# mosfet-drv.net
KiCad netlist of a schematic drawn in EAGLE
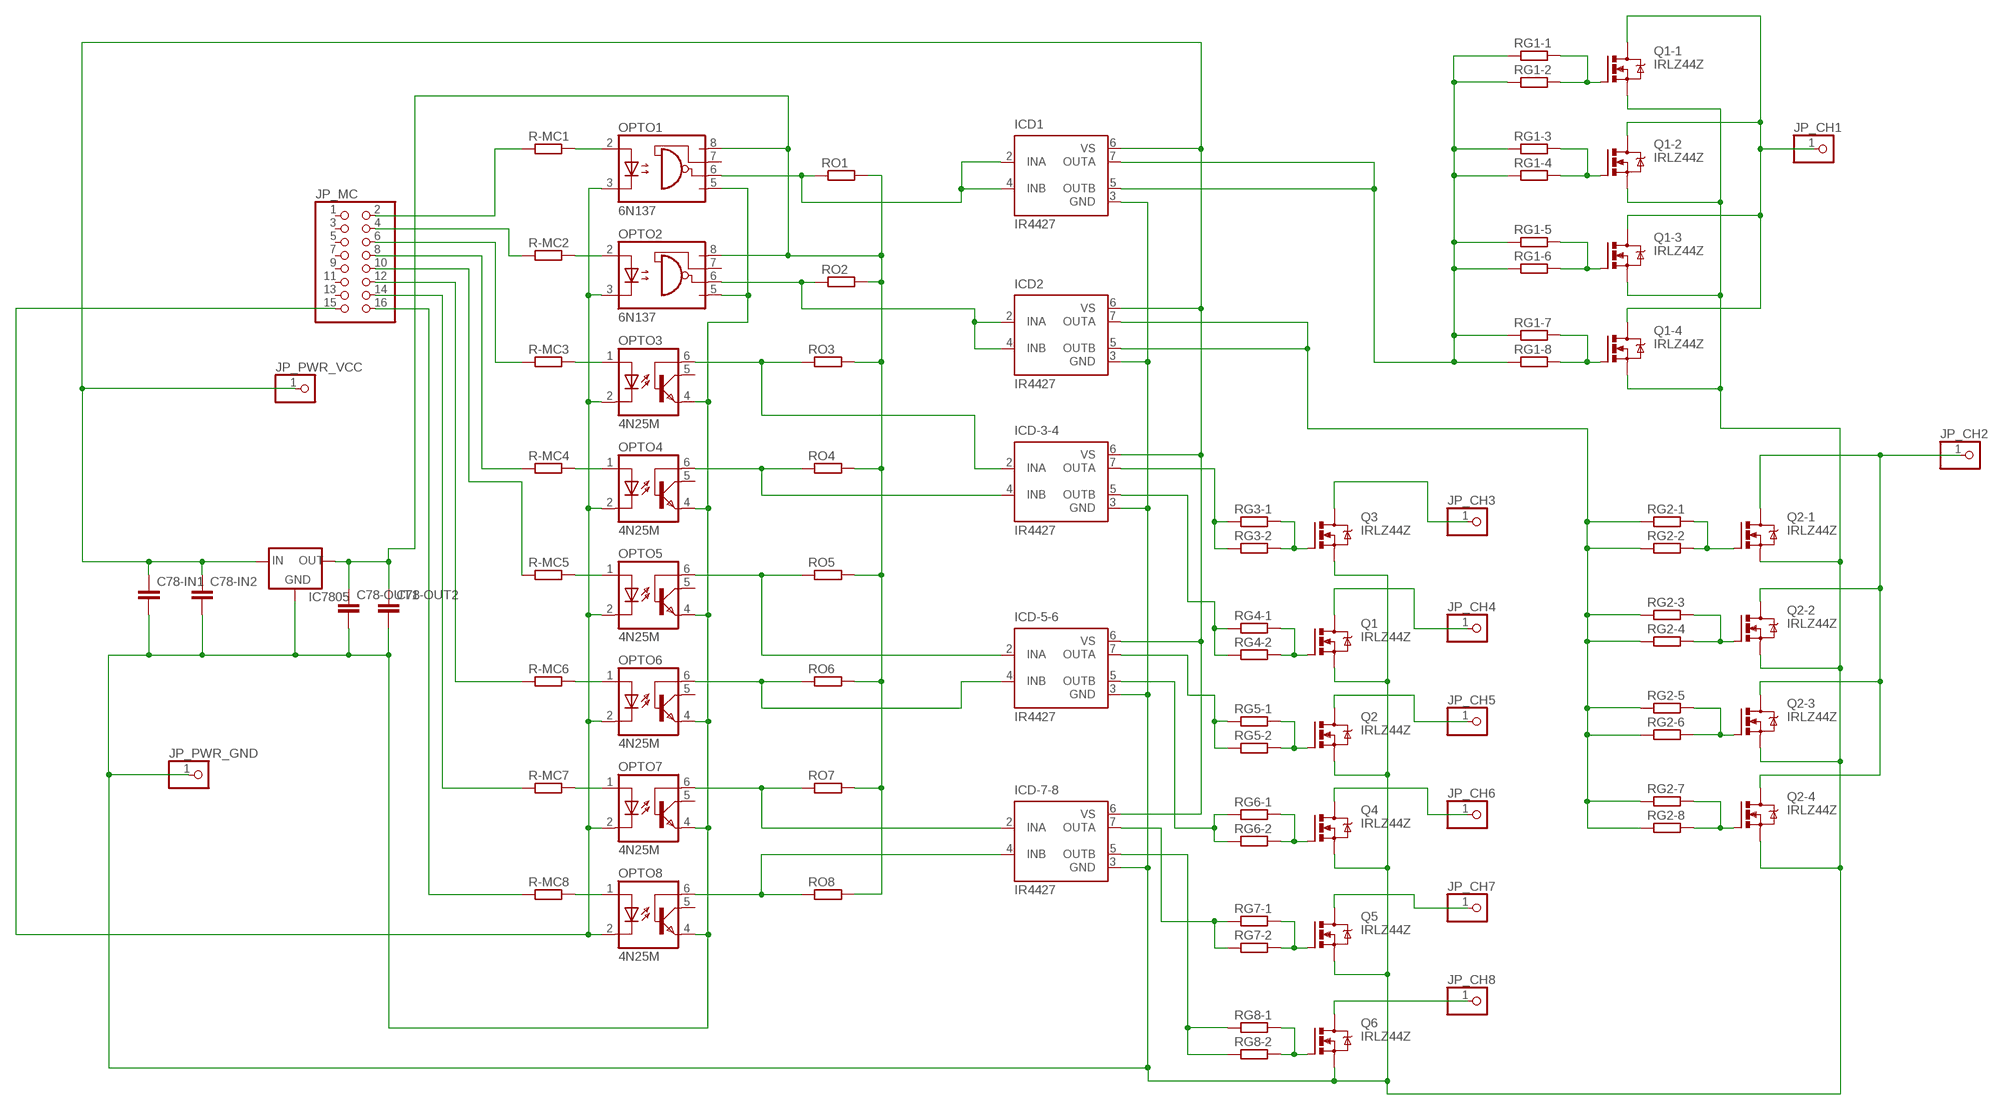
[diagram p0: schematic, sheet 1]

(export (version "E")
  (design (tool "Eeschema 10.0.6"))
  (components
    (comp (ref "C78-IN1")
      (value "C-EU025-060X050")
      (footprint "eagle-import:C025-060X050")
      (libsource (lib "eagle-import") (part "C-EU025-060X050"))
    )
    (comp (ref "C78-IN2")
      (value "C-EU025-060X050")
      (footprint "eagle-import:C025-060X050")
      (libsource (lib "eagle-import") (part "C-EU025-060X050"))
    )
    (comp (ref "C78-OUT1")
      (value "C-EU025-060X050")
      (footprint "eagle-import:C025-060X050")
      (libsource (lib "eagle-import") (part "C-EU025-060X050"))
    )
    (comp (ref "C78-OUT2")
      (value "C-EU025-060X050")
      (footprint "eagle-import:C025-060X050")
      (libsource (lib "eagle-import") (part "C-EU025-060X050"))
    )
    (comp (ref "IC7805")
      (value "78XXS")
      (footprint "eagle-import:78XXS")
      (libsource (lib "eagle-import") (part "78XXS"))
    )
    (comp (ref "ICD-3-4")
      (value "IR4427")
      (footprint "eagle-import:DIL08")
      (fields (field (name "MF") "INTERNATIONAL RECTIFIER(IR)"))
      (libsource (lib "eagle-import") (part "IR4427"))
    )
    (comp (ref "ICD-5-6")
      (value "IR4427")
      (footprint "eagle-import:DIL08")
      (fields (field (name "MF") "INTERNATIONAL RECTIFIER(IR)"))
      (libsource (lib "eagle-import") (part "IR4427"))
    )
    (comp (ref "ICD-7-8")
      (value "IR4427")
      (footprint "eagle-import:DIL08")
      (fields (field (name "MF") "INTERNATIONAL RECTIFIER(IR)"))
      (libsource (lib "eagle-import") (part "IR4427"))
    )
    (comp (ref "ICD1")
      (value "IR4427")
      (footprint "eagle-import:DIL08")
      (fields (field (name "MF") "INTERNATIONAL RECTIFIER(IR)"))
      (libsource (lib "eagle-import") (part "IR4427"))
    )
    (comp (ref "ICD2")
      (value "IR4427")
      (footprint "eagle-import:DIL08")
      (fields (field (name "MF") "INTERNATIONAL RECTIFIER(IR)"))
      (libsource (lib "eagle-import") (part "IR4427"))
    )
    (comp (ref "JP_CH1")
      (value "PINHD-1X1")
      (footprint "eagle-import:1X01")
      (libsource (lib "eagle-import") (part "PINHD-1X1"))
    )
    (comp (ref "JP_CH2")
      (value "PINHD-1X1")
      (footprint "eagle-import:1X01")
      (libsource (lib "eagle-import") (part "PINHD-1X1"))
    )
    (comp (ref "JP_CH3")
      (value "PINHD-1X1")
      (footprint "eagle-import:1X01")
      (libsource (lib "eagle-import") (part "PINHD-1X1"))
    )
    (comp (ref "JP_CH4")
      (value "PINHD-1X1")
      (footprint "eagle-import:1X01")
      (libsource (lib "eagle-import") (part "PINHD-1X1"))
    )
    (comp (ref "JP_CH5")
      (value "PINHD-1X1")
      (footprint "eagle-import:1X01")
      (libsource (lib "eagle-import") (part "PINHD-1X1"))
    )
    (comp (ref "JP_CH6")
      (value "PINHD-1X1")
      (footprint "eagle-import:1X01")
      (libsource (lib "eagle-import") (part "PINHD-1X1"))
    )
    (comp (ref "JP_CH7")
      (value "PINHD-1X1")
      (footprint "eagle-import:1X01")
      (libsource (lib "eagle-import") (part "PINHD-1X1"))
    )
    (comp (ref "JP_CH8")
      (value "PINHD-1X1")
      (footprint "eagle-import:1X01")
      (libsource (lib "eagle-import") (part "PINHD-1X1"))
    )
    (comp (ref "JP_MC")
      (value "PINHD-2X8")
      (footprint "eagle-import:2X08")
      (libsource (lib "eagle-import") (part "PINHD-2X8"))
    )
    (comp (ref "JP_PWR_GND")
      (value "PINHD-1X1")
      (footprint "eagle-import:1X01")
      (libsource (lib "eagle-import") (part "PINHD-1X1"))
    )
    (comp (ref "JP_PWR_VCC")
      (value "PINHD-1X1")
      (footprint "eagle-import:1X01")
      (libsource (lib "eagle-import") (part "PINHD-1X1"))
    )
    (comp (ref "OPTO1")
      (value "6N137")
      (footprint "eagle-import:DIL08")
      (libsource (lib "eagle-import") (part "6N137"))
    )
    (comp (ref "OPTO2")
      (value "6N137")
      (footprint "eagle-import:DIL08")
      (libsource (lib "eagle-import") (part "6N137"))
    )
    (comp (ref "OPTO3")
      (value "4N25M")
      (footprint "eagle-import:DIL06")
      (fields (field (name "MPN") "4N25-M"))
      (libsource (lib "eagle-import") (part "4N?M25"))
    )
    (comp (ref "OPTO4")
      (value "4N25M")
      (footprint "eagle-import:DIL06")
      (fields (field (name "MPN") "4N25-M"))
      (libsource (lib "eagle-import") (part "4N?M25"))
    )
    (comp (ref "OPTO5")
      (value "4N25M")
      (footprint "eagle-import:DIL06")
      (fields (field (name "MPN") "4N25-M"))
      (libsource (lib "eagle-import") (part "4N?M25"))
    )
    (comp (ref "OPTO6")
      (value "4N25M")
      (footprint "eagle-import:DIL06")
      (fields (field (name "MPN") "4N25-M"))
      (libsource (lib "eagle-import") (part "4N?M25"))
    )
    (comp (ref "OPTO7")
      (value "4N25M")
      (footprint "eagle-import:DIL06")
      (fields (field (name "MPN") "4N25-M"))
      (libsource (lib "eagle-import") (part "4N?M25"))
    )
    (comp (ref "OPTO8")
      (value "4N25M")
      (footprint "eagle-import:DIL06")
      (fields (field (name "MPN") "4N25-M"))
      (libsource (lib "eagle-import") (part "4N?M25"))
    )
    (comp (ref "Q1")
      (value "IRLZ44Z")
      (footprint "eagle-import:TO220BH")
      (libsource (lib "eagle-import") (part "IRLZ44Z"))
    )
    (comp (ref "Q1-1")
      (value "IRLZ44Z")
      (footprint "eagle-import:TO220BH")
      (libsource (lib "eagle-import") (part "IRLZ44Z"))
    )
    (comp (ref "Q1-2")
      (value "IRLZ44Z")
      (footprint "eagle-import:TO220BH")
      (libsource (lib "eagle-import") (part "IRLZ44Z"))
    )
    (comp (ref "Q1-3")
      (value "IRLZ44Z")
      (footprint "eagle-import:TO220BH")
      (libsource (lib "eagle-import") (part "IRLZ44Z"))
    )
    (comp (ref "Q1-4")
      (value "IRLZ44Z")
      (footprint "eagle-import:TO220BH")
      (libsource (lib "eagle-import") (part "IRLZ44Z"))
    )
    (comp (ref "Q2")
      (value "IRLZ44Z")
      (footprint "eagle-import:TO220BH")
      (libsource (lib "eagle-import") (part "IRLZ44Z"))
    )
    (comp (ref "Q2-1")
      (value "IRLZ44Z")
      (footprint "eagle-import:TO220BH")
      (libsource (lib "eagle-import") (part "IRLZ44Z"))
    )
    (comp (ref "Q2-2")
      (value "IRLZ44Z")
      (footprint "eagle-import:TO220BH")
      (libsource (lib "eagle-import") (part "IRLZ44Z"))
    )
    (comp (ref "Q2-3")
      (value "IRLZ44Z")
      (footprint "eagle-import:TO220BH")
      (libsource (lib "eagle-import") (part "IRLZ44Z"))
    )
    (comp (ref "Q2-4")
      (value "IRLZ44Z")
      (footprint "eagle-import:TO220BH")
      (libsource (lib "eagle-import") (part "IRLZ44Z"))
    )
    (comp (ref "Q3")
      (value "IRLZ44Z")
      (footprint "eagle-import:TO220BH")
      (libsource (lib "eagle-import") (part "IRLZ44Z"))
    )
    (comp (ref "Q4")
      (value "IRLZ44Z")
      (footprint "eagle-import:TO220BH")
      (libsource (lib "eagle-import") (part "IRLZ44Z"))
    )
    (comp (ref "Q5")
      (value "IRLZ44Z")
      (footprint "eagle-import:TO220BH")
      (libsource (lib "eagle-import") (part "IRLZ44Z"))
    )
    (comp (ref "Q6")
      (value "IRLZ44Z")
      (footprint "eagle-import:TO220BH")
      (libsource (lib "eagle-import") (part "IRLZ44Z"))
    )
    (comp (ref "R-MC1")
      (value "R-EU_0207/15")
      (footprint "eagle-import:0207_15")
      (libsource (lib "eagle-import") (part "R-EU_0207/15"))
    )
    (comp (ref "R-MC2")
      (value "R-EU_0207/15")
      (footprint "eagle-import:0207_15")
      (libsource (lib "eagle-import") (part "R-EU_0207/15"))
    )
    (comp (ref "R-MC3")
      (value "R-EU_0207/15")
      (footprint "eagle-import:0207_15")
      (libsource (lib "eagle-import") (part "R-EU_0207/15"))
    )
    (comp (ref "R-MC4")
      (value "R-EU_0207/15")
      (footprint "eagle-import:0207_15")
      (libsource (lib "eagle-import") (part "R-EU_0207/15"))
    )
    (comp (ref "R-MC5")
      (value "R-EU_0207/15")
      (footprint "eagle-import:0207_15")
      (libsource (lib "eagle-import") (part "R-EU_0207/15"))
    )
    (comp (ref "R-MC6")
      (value "R-EU_0207/15")
      (footprint "eagle-import:0207_15")
      (libsource (lib "eagle-import") (part "R-EU_0207/15"))
    )
    (comp (ref "R-MC7")
      (value "R-EU_0207/15")
      (footprint "eagle-import:0207_15")
      (libsource (lib "eagle-import") (part "R-EU_0207/15"))
    )
    (comp (ref "R-MC8")
      (value "R-EU_0207/15")
      (footprint "eagle-import:0207_15")
      (libsource (lib "eagle-import") (part "R-EU_0207/15"))
    )
    (comp (ref "RG1-1")
      (value "R-EU_0207/15")
      (footprint "eagle-import:0207_15")
      (libsource (lib "eagle-import") (part "R-EU_0207/15"))
    )
    (comp (ref "RG1-2")
      (value "R-EU_0207/15")
      (footprint "eagle-import:0207_15")
      (libsource (lib "eagle-import") (part "R-EU_0207/15"))
    )
    (comp (ref "RG1-3")
      (value "R-EU_0207/15")
      (footprint "eagle-import:0207_15")
      (libsource (lib "eagle-import") (part "R-EU_0207/15"))
    )
    (comp (ref "RG1-4")
      (value "R-EU_0207/15")
      (footprint "eagle-import:0207_15")
      (libsource (lib "eagle-import") (part "R-EU_0207/15"))
    )
    (comp (ref "RG1-5")
      (value "R-EU_0207/15")
      (footprint "eagle-import:0207_15")
      (libsource (lib "eagle-import") (part "R-EU_0207/15"))
    )
    (comp (ref "RG1-6")
      (value "R-EU_0207/15")
      (footprint "eagle-import:0207_15")
      (libsource (lib "eagle-import") (part "R-EU_0207/15"))
    )
    (comp (ref "RG1-7")
      (value "R-EU_0207/15")
      (footprint "eagle-import:0207_15")
      (libsource (lib "eagle-import") (part "R-EU_0207/15"))
    )
    (comp (ref "RG1-8")
      (value "R-EU_0207/15")
      (footprint "eagle-import:0207_15")
      (libsource (lib "eagle-import") (part "R-EU_0207/15"))
    )
    (comp (ref "RG2-1")
      (value "R-EU_0207/15")
      (footprint "eagle-import:0207_15")
      (libsource (lib "eagle-import") (part "R-EU_0207/15"))
    )
    (comp (ref "RG2-2")
      (value "R-EU_0207/15")
      (footprint "eagle-import:0207_15")
      (libsource (lib "eagle-import") (part "R-EU_0207/15"))
    )
    (comp (ref "RG2-3")
      (value "R-EU_0207/15")
      (footprint "eagle-import:0207_15")
      (libsource (lib "eagle-import") (part "R-EU_0207/15"))
    )
    (comp (ref "RG2-4")
      (value "R-EU_0207/15")
      (footprint "eagle-import:0207_15")
      (libsource (lib "eagle-import") (part "R-EU_0207/15"))
    )
    (comp (ref "RG2-5")
      (value "R-EU_0207/15")
      (footprint "eagle-import:0207_15")
      (libsource (lib "eagle-import") (part "R-EU_0207/15"))
    )
    (comp (ref "RG2-6")
      (value "R-EU_0207/15")
      (footprint "eagle-import:0207_15")
      (libsource (lib "eagle-import") (part "R-EU_0207/15"))
    )
    (comp (ref "RG2-7")
      (value "R-EU_0207/15")
      (footprint "eagle-import:0207_15")
      (libsource (lib "eagle-import") (part "R-EU_0207/15"))
    )
    (comp (ref "RG2-8")
      (value "R-EU_0207/15")
      (footprint "eagle-import:0207_15")
      (libsource (lib "eagle-import") (part "R-EU_0207/15"))
    )
    (comp (ref "RG3-1")
      (value "R-EU_0207/15")
      (footprint "eagle-import:0207_15")
      (libsource (lib "eagle-import") (part "R-EU_0207/15"))
    )
    (comp (ref "RG3-2")
      (value "R-EU_0207/15")
      (footprint "eagle-import:0207_15")
      (libsource (lib "eagle-import") (part "R-EU_0207/15"))
    )
    (comp (ref "RG4-1")
      (value "R-EU_0207/15")
      (footprint "eagle-import:0207_15")
      (libsource (lib "eagle-import") (part "R-EU_0207/15"))
    )
    (comp (ref "RG4-2")
      (value "R-EU_0207/15")
      (footprint "eagle-import:0207_15")
      (libsource (lib "eagle-import") (part "R-EU_0207/15"))
    )
    (comp (ref "RG5-1")
      (value "R-EU_0207/15")
      (footprint "eagle-import:0207_15")
      (libsource (lib "eagle-import") (part "R-EU_0207/15"))
    )
    (comp (ref "RG5-2")
      (value "R-EU_0207/15")
      (footprint "eagle-import:0207_15")
      (libsource (lib "eagle-import") (part "R-EU_0207/15"))
    )
    (comp (ref "RG6-1")
      (value "R-EU_0207/15")
      (footprint "eagle-import:0207_15")
      (libsource (lib "eagle-import") (part "R-EU_0207/15"))
    )
    (comp (ref "RG6-2")
      (value "R-EU_0207/15")
      (footprint "eagle-import:0207_15")
      (libsource (lib "eagle-import") (part "R-EU_0207/15"))
    )
    (comp (ref "RG7-1")
      (value "R-EU_0207/15")
      (footprint "eagle-import:0207_15")
      (libsource (lib "eagle-import") (part "R-EU_0207/15"))
    )
    (comp (ref "RG7-2")
      (value "R-EU_0207/15")
      (footprint "eagle-import:0207_15")
      (libsource (lib "eagle-import") (part "R-EU_0207/15"))
    )
    (comp (ref "RG8-1")
      (value "R-EU_0207/15")
      (footprint "eagle-import:0207_15")
      (libsource (lib "eagle-import") (part "R-EU_0207/15"))
    )
    (comp (ref "RG8-2")
      (value "R-EU_0207/15")
      (footprint "eagle-import:0207_15")
      (libsource (lib "eagle-import") (part "R-EU_0207/15"))
    )
    (comp (ref "RO1")
      (value "R-EU_0207/15")
      (footprint "eagle-import:0207_15")
      (libsource (lib "eagle-import") (part "R-EU_0207/15"))
    )
    (comp (ref "RO2")
      (value "R-EU_0207/15")
      (footprint "eagle-import:0207_15")
      (libsource (lib "eagle-import") (part "R-EU_0207/15"))
    )
    (comp (ref "RO3")
      (value "R-EU_0207/15")
      (footprint "eagle-import:0207_15")
      (libsource (lib "eagle-import") (part "R-EU_0207/15"))
    )
    (comp (ref "RO4")
      (value "R-EU_0207/15")
      (footprint "eagle-import:0207_15")
      (libsource (lib "eagle-import") (part "R-EU_0207/15"))
    )
    (comp (ref "RO5")
      (value "R-EU_0207/15")
      (footprint "eagle-import:0207_15")
      (libsource (lib "eagle-import") (part "R-EU_0207/15"))
    )
    (comp (ref "RO6")
      (value "R-EU_0207/15")
      (footprint "eagle-import:0207_15")
      (libsource (lib "eagle-import") (part "R-EU_0207/15"))
    )
    (comp (ref "RO7")
      (value "R-EU_0207/15")
      (footprint "eagle-import:0207_15")
      (libsource (lib "eagle-import") (part "R-EU_0207/15"))
    )
    (comp (ref "RO8")
      (value "R-EU_0207/15")
      (footprint "eagle-import:0207_15")
      (libsource (lib "eagle-import") (part "R-EU_0207/15"))
    )
  )
  (nets
    (net (code "1") (name "Net-(ICD-3-4-GND)") (class "Default")
      (node (ref "C78-IN1") (pin "2") (pinfunction "2_2") (pintype "passive"))
      (node (ref "C78-IN2") (pin "2") (pinfunction "2_2") (pintype "passive"))
      (node (ref "C78-OUT1") (pin "2") (pinfunction "2_2") (pintype "passive"))
      (node (ref "C78-OUT2") (pin "2") (pinfunction "2_2") (pintype "passive"))
      (node (ref "IC7805") (pin "GND") (pinfunction "GND_GND") (pintype "input"))
      (node (ref "ICD-3-4") (pin "3") (pinfunction "GND_3") (pintype "power_in"))
      (node (ref "ICD-5-6") (pin "3") (pinfunction "GND_3") (pintype "power_in"))
      (node (ref "ICD-7-8") (pin "3") (pinfunction "GND_3") (pintype "power_in"))
      (node (ref "ICD1") (pin "3") (pinfunction "GND_3") (pintype "power_in"))
      (node (ref "ICD2") (pin "3") (pinfunction "GND_3") (pintype "power_in"))
      (node (ref "JP_PWR_GND") (pin "1") (pinfunction "1_1") (pintype "passive"))
      (node (ref "OPTO1") (pin "5") (pinfunction "GND_5") (pintype "passive"))
      (node (ref "OPTO2") (pin "5") (pinfunction "GND_5") (pintype "passive"))
      (node (ref "OPTO3") (pin "4") (pinfunction "EMI_4") (pintype "passive"))
      (node (ref "OPTO4") (pin "4") (pinfunction "EMI_4") (pintype "passive"))
      (node (ref "OPTO5") (pin "4") (pinfunction "EMI_4") (pintype "passive"))
      (node (ref "OPTO6") (pin "4") (pinfunction "EMI_4") (pintype "passive"))
      (node (ref "OPTO7") (pin "4") (pinfunction "EMI_4") (pintype "passive"))
      (node (ref "OPTO8") (pin "4") (pinfunction "EMI_4") (pintype "passive"))
      (node (ref "Q1") (pin "S") (pinfunction "S_S") (pintype "passive"))
      (node (ref "Q1-1") (pin "S") (pinfunction "S_S") (pintype "passive"))
      (node (ref "Q1-2") (pin "S") (pinfunction "S_S") (pintype "passive"))
      (node (ref "Q1-3") (pin "S") (pinfunction "S_S") (pintype "passive"))
      (node (ref "Q1-4") (pin "S") (pinfunction "S_S") (pintype "passive"))
      (node (ref "Q2") (pin "S") (pinfunction "S_S") (pintype "passive"))
      (node (ref "Q2-1") (pin "S") (pinfunction "S_S") (pintype "passive"))
      (node (ref "Q2-2") (pin "S") (pinfunction "S_S") (pintype "passive"))
      (node (ref "Q2-3") (pin "S") (pinfunction "S_S") (pintype "passive"))
      (node (ref "Q2-4") (pin "S") (pinfunction "S_S") (pintype "passive"))
      (node (ref "Q3") (pin "S") (pinfunction "S_S") (pintype "passive"))
      (node (ref "Q4") (pin "S") (pinfunction "S_S") (pintype "passive"))
      (node (ref "Q5") (pin "S") (pinfunction "S_S") (pintype "passive"))
      (node (ref "Q6") (pin "S") (pinfunction "S_S") (pintype "passive"))
    )
    (net (code "2") (name "Net-(ICD-3-4-INA)") (class "Default")
      (node (ref "ICD-3-4") (pin "2") (pinfunction "INA_2") (pintype "input"))
      (node (ref "OPTO3") (pin "6") (pinfunction "BAS_6") (pintype "passive"))
      (node (ref "RO3") (pin "1") (pinfunction "1_1") (pintype "passive"))
    )
    (net (code "3") (name "Net-(ICD-3-4-INB)") (class "Default")
      (node (ref "ICD-3-4") (pin "4") (pinfunction "INB_4") (pintype "input"))
      (node (ref "OPTO4") (pin "6") (pinfunction "BAS_6") (pintype "passive"))
      (node (ref "RO4") (pin "1") (pinfunction "1_1") (pintype "passive"))
    )
    (net (code "4") (name "Net-(ICD-3-4-OUTA)") (class "Default")
      (node (ref "ICD-3-4") (pin "7") (pinfunction "OUTA_7") (pintype "output"))
      (node (ref "RG3-1") (pin "1") (pinfunction "1_1") (pintype "passive"))
      (node (ref "RG3-2") (pin "1") (pinfunction "1_1") (pintype "passive"))
    )
    (net (code "5") (name "Net-(ICD-3-4-OUTB)") (class "Default")
      (node (ref "ICD-3-4") (pin "5") (pinfunction "OUTB_5") (pintype "output"))
      (node (ref "RG4-1") (pin "1") (pinfunction "1_1") (pintype "passive"))
      (node (ref "RG4-2") (pin "1") (pinfunction "1_1") (pintype "passive"))
    )
    (net (code "6") (name "Net-(ICD-3-4-VS)") (class "Default")
      (node (ref "C78-IN1") (pin "1") (pinfunction "1_1") (pintype "passive"))
      (node (ref "C78-IN2") (pin "1") (pinfunction "1_1") (pintype "passive"))
      (node (ref "IC7805") (pin "IN") (pinfunction "IN_IN") (pintype "input"))
      (node (ref "ICD-3-4") (pin "6") (pinfunction "VS_6") (pintype "power_in"))
      (node (ref "ICD-5-6") (pin "6") (pinfunction "VS_6") (pintype "power_in"))
      (node (ref "ICD-7-8") (pin "6") (pinfunction "VS_6") (pintype "power_in"))
      (node (ref "ICD1") (pin "6") (pinfunction "VS_6") (pintype "power_in"))
      (node (ref "ICD2") (pin "6") (pinfunction "VS_6") (pintype "power_in"))
      (node (ref "JP_PWR_VCC") (pin "1") (pinfunction "1_1") (pintype "passive"))
    )
    (net (code "7") (name "Net-(ICD-5-6-INA)") (class "Default")
      (node (ref "ICD-5-6") (pin "2") (pinfunction "INA_2") (pintype "input"))
      (node (ref "OPTO5") (pin "6") (pinfunction "BAS_6") (pintype "passive"))
      (node (ref "RO5") (pin "1") (pinfunction "1_1") (pintype "passive"))
    )
    (net (code "8") (name "Net-(ICD-5-6-INB)") (class "Default")
      (node (ref "ICD-5-6") (pin "4") (pinfunction "INB_4") (pintype "input"))
      (node (ref "OPTO6") (pin "6") (pinfunction "BAS_6") (pintype "passive"))
      (node (ref "RO6") (pin "1") (pinfunction "1_1") (pintype "passive"))
    )
    (net (code "9") (name "Net-(ICD-5-6-OUTA)") (class "Default")
      (node (ref "ICD-5-6") (pin "7") (pinfunction "OUTA_7") (pintype "output"))
      (node (ref "RG5-1") (pin "1") (pinfunction "1_1") (pintype "passive"))
      (node (ref "RG5-2") (pin "1") (pinfunction "1_1") (pintype "passive"))
    )
    (net (code "10") (name "Net-(ICD-5-6-OUTB)") (class "Default")
      (node (ref "ICD-5-6") (pin "5") (pinfunction "OUTB_5") (pintype "output"))
      (node (ref "RG6-1") (pin "1") (pinfunction "1_1") (pintype "passive"))
      (node (ref "RG6-2") (pin "1") (pinfunction "1_1") (pintype "passive"))
    )
    (net (code "11") (name "Net-(ICD-7-8-INA)") (class "Default")
      (node (ref "ICD-7-8") (pin "2") (pinfunction "INA_2") (pintype "input"))
      (node (ref "OPTO7") (pin "6") (pinfunction "BAS_6") (pintype "passive"))
      (node (ref "RO7") (pin "1") (pinfunction "1_1") (pintype "passive"))
    )
    (net (code "12") (name "Net-(ICD-7-8-INB)") (class "Default")
      (node (ref "ICD-7-8") (pin "4") (pinfunction "INB_4") (pintype "input"))
      (node (ref "OPTO8") (pin "6") (pinfunction "BAS_6") (pintype "passive"))
      (node (ref "RO8") (pin "1") (pinfunction "1_1") (pintype "passive"))
    )
    (net (code "13") (name "Net-(ICD-7-8-OUTA)") (class "Default")
      (node (ref "ICD-7-8") (pin "7") (pinfunction "OUTA_7") (pintype "output"))
      (node (ref "RG7-1") (pin "1") (pinfunction "1_1") (pintype "passive"))
      (node (ref "RG7-2") (pin "1") (pinfunction "1_1") (pintype "passive"))
    )
    (net (code "14") (name "Net-(ICD-7-8-OUTB)") (class "Default")
      (node (ref "ICD-7-8") (pin "5") (pinfunction "OUTB_5") (pintype "output"))
      (node (ref "RG8-1") (pin "1") (pinfunction "1_1") (pintype "passive"))
      (node (ref "RG8-2") (pin "1") (pinfunction "1_1") (pintype "passive"))
    )
    (net (code "15") (name "Net-(ICD1-INA)") (class "Default")
      (node (ref "ICD1") (pin "2") (pinfunction "INA_2") (pintype "input"))
      (node (ref "ICD1") (pin "4") (pinfunction "INB_4") (pintype "input"))
      (node (ref "OPTO1") (pin "6") (pinfunction "VO_6") (pintype "passive"))
      (node (ref "RO1") (pin "1") (pinfunction "1_1") (pintype "passive"))
    )
    (net (code "16") (name "Net-(ICD1-OUTA)") (class "Default")
      (node (ref "ICD1") (pin "5") (pinfunction "OUTB_5") (pintype "output"))
      (node (ref "ICD1") (pin "7") (pinfunction "OUTA_7") (pintype "output"))
      (node (ref "RG1-1") (pin "1") (pinfunction "1_1") (pintype "passive"))
      (node (ref "RG1-2") (pin "1") (pinfunction "1_1") (pintype "passive"))
      (node (ref "RG1-3") (pin "1") (pinfunction "1_1") (pintype "passive"))
      (node (ref "RG1-4") (pin "1") (pinfunction "1_1") (pintype "passive"))
      (node (ref "RG1-5") (pin "1") (pinfunction "1_1") (pintype "passive"))
      (node (ref "RG1-6") (pin "1") (pinfunction "1_1") (pintype "passive"))
      (node (ref "RG1-7") (pin "1") (pinfunction "1_1") (pintype "passive"))
      (node (ref "RG1-8") (pin "1") (pinfunction "1_1") (pintype "passive"))
    )
    (net (code "17") (name "Net-(ICD2-INA)") (class "Default")
      (node (ref "ICD2") (pin "2") (pinfunction "INA_2") (pintype "input"))
      (node (ref "ICD2") (pin "4") (pinfunction "INB_4") (pintype "input"))
      (node (ref "OPTO2") (pin "6") (pinfunction "VO_6") (pintype "passive"))
      (node (ref "RO2") (pin "1") (pinfunction "1_1") (pintype "passive"))
    )
    (net (code "18") (name "Net-(ICD2-OUTA)") (class "Default")
      (node (ref "ICD2") (pin "5") (pinfunction "OUTB_5") (pintype "output"))
      (node (ref "ICD2") (pin "7") (pinfunction "OUTA_7") (pintype "output"))
      (node (ref "RG2-1") (pin "1") (pinfunction "1_1") (pintype "passive"))
      (node (ref "RG2-2") (pin "1") (pinfunction "1_1") (pintype "passive"))
      (node (ref "RG2-3") (pin "1") (pinfunction "1_1") (pintype "passive"))
      (node (ref "RG2-4") (pin "1") (pinfunction "1_1") (pintype "passive"))
      (node (ref "RG2-5") (pin "1") (pinfunction "1_1") (pintype "passive"))
      (node (ref "RG2-6") (pin "1") (pinfunction "1_1") (pintype "passive"))
      (node (ref "RG2-7") (pin "1") (pinfunction "1_1") (pintype "passive"))
      (node (ref "RG2-8") (pin "1") (pinfunction "1_1") (pintype "passive"))
    )
    (net (code "19") (name "Net-(JP_CH1-Pad1)") (class "Default")
      (node (ref "JP_CH1") (pin "1") (pinfunction "1_1") (pintype "passive"))
      (node (ref "Q1-1") (pin "D") (pinfunction "D_D") (pintype "passive"))
      (node (ref "Q1-2") (pin "D") (pinfunction "D_D") (pintype "passive"))
      (node (ref "Q1-3") (pin "D") (pinfunction "D_D") (pintype "passive"))
      (node (ref "Q1-4") (pin "D") (pinfunction "D_D") (pintype "passive"))
    )
    (net (code "20") (name "Net-(JP_CH2-Pad1)") (class "Default")
      (node (ref "JP_CH2") (pin "1") (pinfunction "1_1") (pintype "passive"))
      (node (ref "Q2-1") (pin "D") (pinfunction "D_D") (pintype "passive"))
      (node (ref "Q2-2") (pin "D") (pinfunction "D_D") (pintype "passive"))
      (node (ref "Q2-3") (pin "D") (pinfunction "D_D") (pintype "passive"))
      (node (ref "Q2-4") (pin "D") (pinfunction "D_D") (pintype "passive"))
    )
    (net (code "21") (name "Net-(JP_CH3-Pad1)") (class "Default")
      (node (ref "JP_CH3") (pin "1") (pinfunction "1_1") (pintype "passive"))
      (node (ref "Q3") (pin "D") (pinfunction "D_D") (pintype "passive"))
    )
    (net (code "22") (name "Net-(JP_CH4-Pad1)") (class "Default")
      (node (ref "JP_CH4") (pin "1") (pinfunction "1_1") (pintype "passive"))
      (node (ref "Q1") (pin "D") (pinfunction "D_D") (pintype "passive"))
    )
    (net (code "23") (name "Net-(JP_CH5-Pad1)") (class "Default")
      (node (ref "JP_CH5") (pin "1") (pinfunction "1_1") (pintype "passive"))
      (node (ref "Q2") (pin "D") (pinfunction "D_D") (pintype "passive"))
    )
    (net (code "24") (name "Net-(JP_CH6-Pad1)") (class "Default")
      (node (ref "JP_CH6") (pin "1") (pinfunction "1_1") (pintype "passive"))
      (node (ref "Q4") (pin "D") (pinfunction "D_D") (pintype "passive"))
    )
    (net (code "25") (name "Net-(JP_CH7-Pad1)") (class "Default")
      (node (ref "JP_CH7") (pin "1") (pinfunction "1_1") (pintype "passive"))
      (node (ref "Q5") (pin "D") (pinfunction "D_D") (pintype "passive"))
    )
    (net (code "26") (name "Net-(JP_CH8-Pad1)") (class "Default")
      (node (ref "JP_CH8") (pin "1") (pinfunction "1_1") (pintype "passive"))
      (node (ref "Q6") (pin "D") (pinfunction "D_D") (pintype "passive"))
    )
    (net (code "27") (name "Net-(JP_MC-Pad2)") (class "Default")
      (node (ref "JP_MC") (pin "2") (pinfunction "2_2") (pintype "passive"))
      (node (ref "R-MC1") (pin "1") (pinfunction "1_1") (pintype "passive"))
    )
    (net (code "28") (name "Net-(JP_MC-Pad4)") (class "Default")
      (node (ref "JP_MC") (pin "4") (pinfunction "4_4") (pintype "passive"))
      (node (ref "R-MC2") (pin "1") (pinfunction "1_1") (pintype "passive"))
    )
    (net (code "29") (name "Net-(JP_MC-Pad6)") (class "Default")
      (node (ref "JP_MC") (pin "6") (pinfunction "6_6") (pintype "passive"))
      (node (ref "R-MC3") (pin "1") (pinfunction "1_1") (pintype "passive"))
    )
    (net (code "30") (name "Net-(JP_MC-Pad8)") (class "Default")
      (node (ref "JP_MC") (pin "8") (pinfunction "8_8") (pintype "passive"))
      (node (ref "R-MC4") (pin "1") (pinfunction "1_1") (pintype "passive"))
    )
    (net (code "31") (name "Net-(JP_MC-Pad10)") (class "Default")
      (node (ref "JP_MC") (pin "10") (pinfunction "10_10") (pintype "passive"))
      (node (ref "R-MC5") (pin "1") (pinfunction "1_1") (pintype "passive"))
    )
    (net (code "32") (name "Net-(JP_MC-Pad12)") (class "Default")
      (node (ref "JP_MC") (pin "12") (pinfunction "12_12") (pintype "passive"))
      (node (ref "R-MC6") (pin "1") (pinfunction "1_1") (pintype "passive"))
    )
    (net (code "33") (name "Net-(JP_MC-Pad14)") (class "Default")
      (node (ref "JP_MC") (pin "14") (pinfunction "14_14") (pintype "passive"))
      (node (ref "R-MC7") (pin "1") (pinfunction "1_1") (pintype "passive"))
    )
    (net (code "34") (name "Net-(JP_MC-Pad16)") (class "Default")
      (node (ref "JP_MC") (pin "16") (pinfunction "16_16") (pintype "passive"))
      (node (ref "R-MC8") (pin "1") (pinfunction "1_1") (pintype "passive"))
    )
    (net (code "35") (name "Net-(OPTO1-A)") (class "Default")
      (node (ref "OPTO1") (pin "2") (pinfunction "A_2") (pintype "passive"))
      (node (ref "R-MC1") (pin "2") (pinfunction "2_2") (pintype "passive"))
    )
    (net (code "36") (name "Net-(OPTO1-C)") (class "Default")
      (node (ref "JP_MC") (pin "15") (pinfunction "15_15") (pintype "passive"))
      (node (ref "OPTO1") (pin "3") (pinfunction "C_3") (pintype "passive"))
      (node (ref "OPTO2") (pin "3") (pinfunction "C_3") (pintype "passive"))
      (node (ref "OPTO3") (pin "2") (pinfunction "C_2") (pintype "passive"))
      (node (ref "OPTO4") (pin "2") (pinfunction "C_2") (pintype "passive"))
      (node (ref "OPTO5") (pin "2") (pinfunction "C_2") (pintype "passive"))
      (node (ref "OPTO6") (pin "2") (pinfunction "C_2") (pintype "passive"))
      (node (ref "OPTO7") (pin "2") (pinfunction "C_2") (pintype "passive"))
      (node (ref "OPTO8") (pin "2") (pinfunction "C_2") (pintype "passive"))
    )
    (net (code "37") (name "Net-(OPTO1-VCC)") (class "Default")
      (node (ref "C78-OUT1") (pin "1") (pinfunction "1_1") (pintype "passive"))
      (node (ref "C78-OUT2") (pin "1") (pinfunction "1_1") (pintype "passive"))
      (node (ref "IC7805") (pin "OUT") (pinfunction "OUT_OUT") (pintype "passive"))
      (node (ref "OPTO1") (pin "8") (pinfunction "VCC_8") (pintype "passive"))
      (node (ref "OPTO2") (pin "8") (pinfunction "VCC_8") (pintype "passive"))
      (node (ref "RO1") (pin "2") (pinfunction "2_2") (pintype "passive"))
      (node (ref "RO2") (pin "2") (pinfunction "2_2") (pintype "passive"))
      (node (ref "RO3") (pin "2") (pinfunction "2_2") (pintype "passive"))
      (node (ref "RO4") (pin "2") (pinfunction "2_2") (pintype "passive"))
      (node (ref "RO5") (pin "2") (pinfunction "2_2") (pintype "passive"))
      (node (ref "RO6") (pin "2") (pinfunction "2_2") (pintype "passive"))
      (node (ref "RO7") (pin "2") (pinfunction "2_2") (pintype "passive"))
      (node (ref "RO8") (pin "2") (pinfunction "2_2") (pintype "passive"))
    )
    (net (code "38") (name "Net-(OPTO2-A)") (class "Default")
      (node (ref "OPTO2") (pin "2") (pinfunction "A_2") (pintype "passive"))
      (node (ref "R-MC2") (pin "2") (pinfunction "2_2") (pintype "passive"))
    )
    (net (code "39") (name "Net-(OPTO3-A)") (class "Default")
      (node (ref "OPTO3") (pin "1") (pinfunction "A_1") (pintype "passive"))
      (node (ref "R-MC3") (pin "2") (pinfunction "2_2") (pintype "passive"))
    )
    (net (code "40") (name "Net-(OPTO4-A)") (class "Default")
      (node (ref "OPTO4") (pin "1") (pinfunction "A_1") (pintype "passive"))
      (node (ref "R-MC4") (pin "2") (pinfunction "2_2") (pintype "passive"))
    )
    (net (code "41") (name "Net-(OPTO5-A)") (class "Default")
      (node (ref "OPTO5") (pin "1") (pinfunction "A_1") (pintype "passive"))
      (node (ref "R-MC5") (pin "2") (pinfunction "2_2") (pintype "passive"))
    )
    (net (code "42") (name "Net-(OPTO6-A)") (class "Default")
      (node (ref "OPTO6") (pin "1") (pinfunction "A_1") (pintype "passive"))
      (node (ref "R-MC6") (pin "2") (pinfunction "2_2") (pintype "passive"))
    )
    (net (code "43") (name "Net-(OPTO7-A)") (class "Default")
      (node (ref "OPTO7") (pin "1") (pinfunction "A_1") (pintype "passive"))
      (node (ref "R-MC7") (pin "2") (pinfunction "2_2") (pintype "passive"))
    )
    (net (code "44") (name "Net-(OPTO8-A)") (class "Default")
      (node (ref "OPTO8") (pin "1") (pinfunction "A_1") (pintype "passive"))
      (node (ref "R-MC8") (pin "2") (pinfunction "2_2") (pintype "passive"))
    )
    (net (code "45") (name "Net-(Q1-1-PadG)") (class "Default")
      (node (ref "Q1-1") (pin "G") (pinfunction "G_G") (pintype "passive"))
      (node (ref "RG1-1") (pin "2") (pinfunction "2_2") (pintype "passive"))
      (node (ref "RG1-2") (pin "2") (pinfunction "2_2") (pintype "passive"))
    )
    (net (code "46") (name "Net-(Q1-2-PadG)") (class "Default")
      (node (ref "Q1-2") (pin "G") (pinfunction "G_G") (pintype "passive"))
      (node (ref "RG1-3") (pin "2") (pinfunction "2_2") (pintype "passive"))
      (node (ref "RG1-4") (pin "2") (pinfunction "2_2") (pintype "passive"))
    )
    (net (code "47") (name "Net-(Q1-3-PadG)") (class "Default")
      (node (ref "Q1-3") (pin "G") (pinfunction "G_G") (pintype "passive"))
      (node (ref "RG1-5") (pin "2") (pinfunction "2_2") (pintype "passive"))
      (node (ref "RG1-6") (pin "2") (pinfunction "2_2") (pintype "passive"))
    )
    (net (code "48") (name "Net-(Q1-4-PadG)") (class "Default")
      (node (ref "Q1-4") (pin "G") (pinfunction "G_G") (pintype "passive"))
      (node (ref "RG1-7") (pin "2") (pinfunction "2_2") (pintype "passive"))
      (node (ref "RG1-8") (pin "2") (pinfunction "2_2") (pintype "passive"))
    )
    (net (code "49") (name "Net-(Q1-PadG)") (class "Default")
      (node (ref "Q1") (pin "G") (pinfunction "G_G") (pintype "passive"))
      (node (ref "RG4-1") (pin "2") (pinfunction "2_2") (pintype "passive"))
      (node (ref "RG4-2") (pin "2") (pinfunction "2_2") (pintype "passive"))
    )
    (net (code "50") (name "Net-(Q2-1-PadG)") (class "Default")
      (node (ref "Q2-1") (pin "G") (pinfunction "G_G") (pintype "passive"))
      (node (ref "RG2-1") (pin "2") (pinfunction "2_2") (pintype "passive"))
      (node (ref "RG2-2") (pin "2") (pinfunction "2_2") (pintype "passive"))
    )
    (net (code "51") (name "Net-(Q2-2-PadG)") (class "Default")
      (node (ref "Q2-2") (pin "G") (pinfunction "G_G") (pintype "passive"))
      (node (ref "RG2-3") (pin "2") (pinfunction "2_2") (pintype "passive"))
      (node (ref "RG2-4") (pin "2") (pinfunction "2_2") (pintype "passive"))
    )
    (net (code "52") (name "Net-(Q2-3-PadG)") (class "Default")
      (node (ref "Q2-3") (pin "G") (pinfunction "G_G") (pintype "passive"))
      (node (ref "RG2-5") (pin "2") (pinfunction "2_2") (pintype "passive"))
      (node (ref "RG2-6") (pin "2") (pinfunction "2_2") (pintype "passive"))
    )
    (net (code "53") (name "Net-(Q2-4-PadG)") (class "Default")
      (node (ref "Q2-4") (pin "G") (pinfunction "G_G") (pintype "passive"))
      (node (ref "RG2-7") (pin "2") (pinfunction "2_2") (pintype "passive"))
      (node (ref "RG2-8") (pin "2") (pinfunction "2_2") (pintype "passive"))
    )
    (net (code "54") (name "Net-(Q2-PadG)") (class "Default")
      (node (ref "Q2") (pin "G") (pinfunction "G_G") (pintype "passive"))
      (node (ref "RG5-1") (pin "2") (pinfunction "2_2") (pintype "passive"))
      (node (ref "RG5-2") (pin "2") (pinfunction "2_2") (pintype "passive"))
    )
    (net (code "55") (name "Net-(Q3-PadG)") (class "Default")
      (node (ref "Q3") (pin "G") (pinfunction "G_G") (pintype "passive"))
      (node (ref "RG3-1") (pin "2") (pinfunction "2_2") (pintype "passive"))
      (node (ref "RG3-2") (pin "2") (pinfunction "2_2") (pintype "passive"))
    )
    (net (code "56") (name "Net-(Q4-PadG)") (class "Default")
      (node (ref "Q4") (pin "G") (pinfunction "G_G") (pintype "passive"))
      (node (ref "RG6-1") (pin "2") (pinfunction "2_2") (pintype "passive"))
      (node (ref "RG6-2") (pin "2") (pinfunction "2_2") (pintype "passive"))
    )
    (net (code "57") (name "Net-(Q5-PadG)") (class "Default")
      (node (ref "Q5") (pin "G") (pinfunction "G_G") (pintype "passive"))
      (node (ref "RG7-1") (pin "2") (pinfunction "2_2") (pintype "passive"))
      (node (ref "RG7-2") (pin "2") (pinfunction "2_2") (pintype "passive"))
    )
    (net (code "58") (name "Net-(Q6-PadG)") (class "Default")
      (node (ref "Q6") (pin "G") (pinfunction "G_G") (pintype "passive"))
      (node (ref "RG8-1") (pin "2") (pinfunction "2_2") (pintype "passive"))
      (node (ref "RG8-2") (pin "2") (pinfunction "2_2") (pintype "passive"))
    )
    (net (code "59") (name "unconnected-(JP_MC-Pad1)") (class "Default")
      (node (ref "JP_MC") (pin "1") (pinfunction "1_1") (pintype "passive"))
    )
    (net (code "60") (name "unconnected-(JP_MC-Pad3)") (class "Default")
      (node (ref "JP_MC") (pin "3") (pinfunction "3_3") (pintype "passive"))
    )
    (net (code "61") (name "unconnected-(JP_MC-Pad5)") (class "Default")
      (node (ref "JP_MC") (pin "5") (pinfunction "5_5") (pintype "passive"))
    )
    (net (code "62") (name "unconnected-(JP_MC-Pad7)") (class "Default")
      (node (ref "JP_MC") (pin "7") (pinfunction "7_7") (pintype "passive"))
    )
    (net (code "63") (name "unconnected-(JP_MC-Pad9)") (class "Default")
      (node (ref "JP_MC") (pin "9") (pinfunction "9_9") (pintype "passive"))
    )
    (net (code "64") (name "unconnected-(JP_MC-Pad11)") (class "Default")
      (node (ref "JP_MC") (pin "11") (pinfunction "11_11") (pintype "passive"))
    )
    (net (code "65") (name "unconnected-(JP_MC-Pad13)") (class "Default")
      (node (ref "JP_MC") (pin "13") (pinfunction "13_13") (pintype "passive"))
    )
    (net (code "66") (name "unconnected-(OPTO1-VE-Pad7)") (class "Default")
      (node (ref "OPTO1") (pin "7") (pinfunction "VE_7") (pintype "passive"))
    )
    (net (code "67") (name "unconnected-(OPTO2-VE-Pad7)") (class "Default")
      (node (ref "OPTO2") (pin "7") (pinfunction "VE_7") (pintype "passive"))
    )
    (net (code "68") (name "unconnected-(OPTO3-COL-Pad5)") (class "Default")
      (node (ref "OPTO3") (pin "5") (pinfunction "COL_5") (pintype "passive"))
    )
    (net (code "69") (name "unconnected-(OPTO4-COL-Pad5)") (class "Default")
      (node (ref "OPTO4") (pin "5") (pinfunction "COL_5") (pintype "passive"))
    )
    (net (code "70") (name "unconnected-(OPTO5-COL-Pad5)") (class "Default")
      (node (ref "OPTO5") (pin "5") (pinfunction "COL_5") (pintype "passive"))
    )
    (net (code "71") (name "unconnected-(OPTO6-COL-Pad5)") (class "Default")
      (node (ref "OPTO6") (pin "5") (pinfunction "COL_5") (pintype "passive"))
    )
    (net (code "72") (name "unconnected-(OPTO7-COL-Pad5)") (class "Default")
      (node (ref "OPTO7") (pin "5") (pinfunction "COL_5") (pintype "passive"))
    )
    (net (code "73") (name "unconnected-(OPTO8-COL-Pad5)") (class "Default")
      (node (ref "OPTO8") (pin "5") (pinfunction "COL_5") (pintype "passive"))
    )
  )
)
